# aquapi2.net
KiCad netlist of a schematic drawn in EAGLE
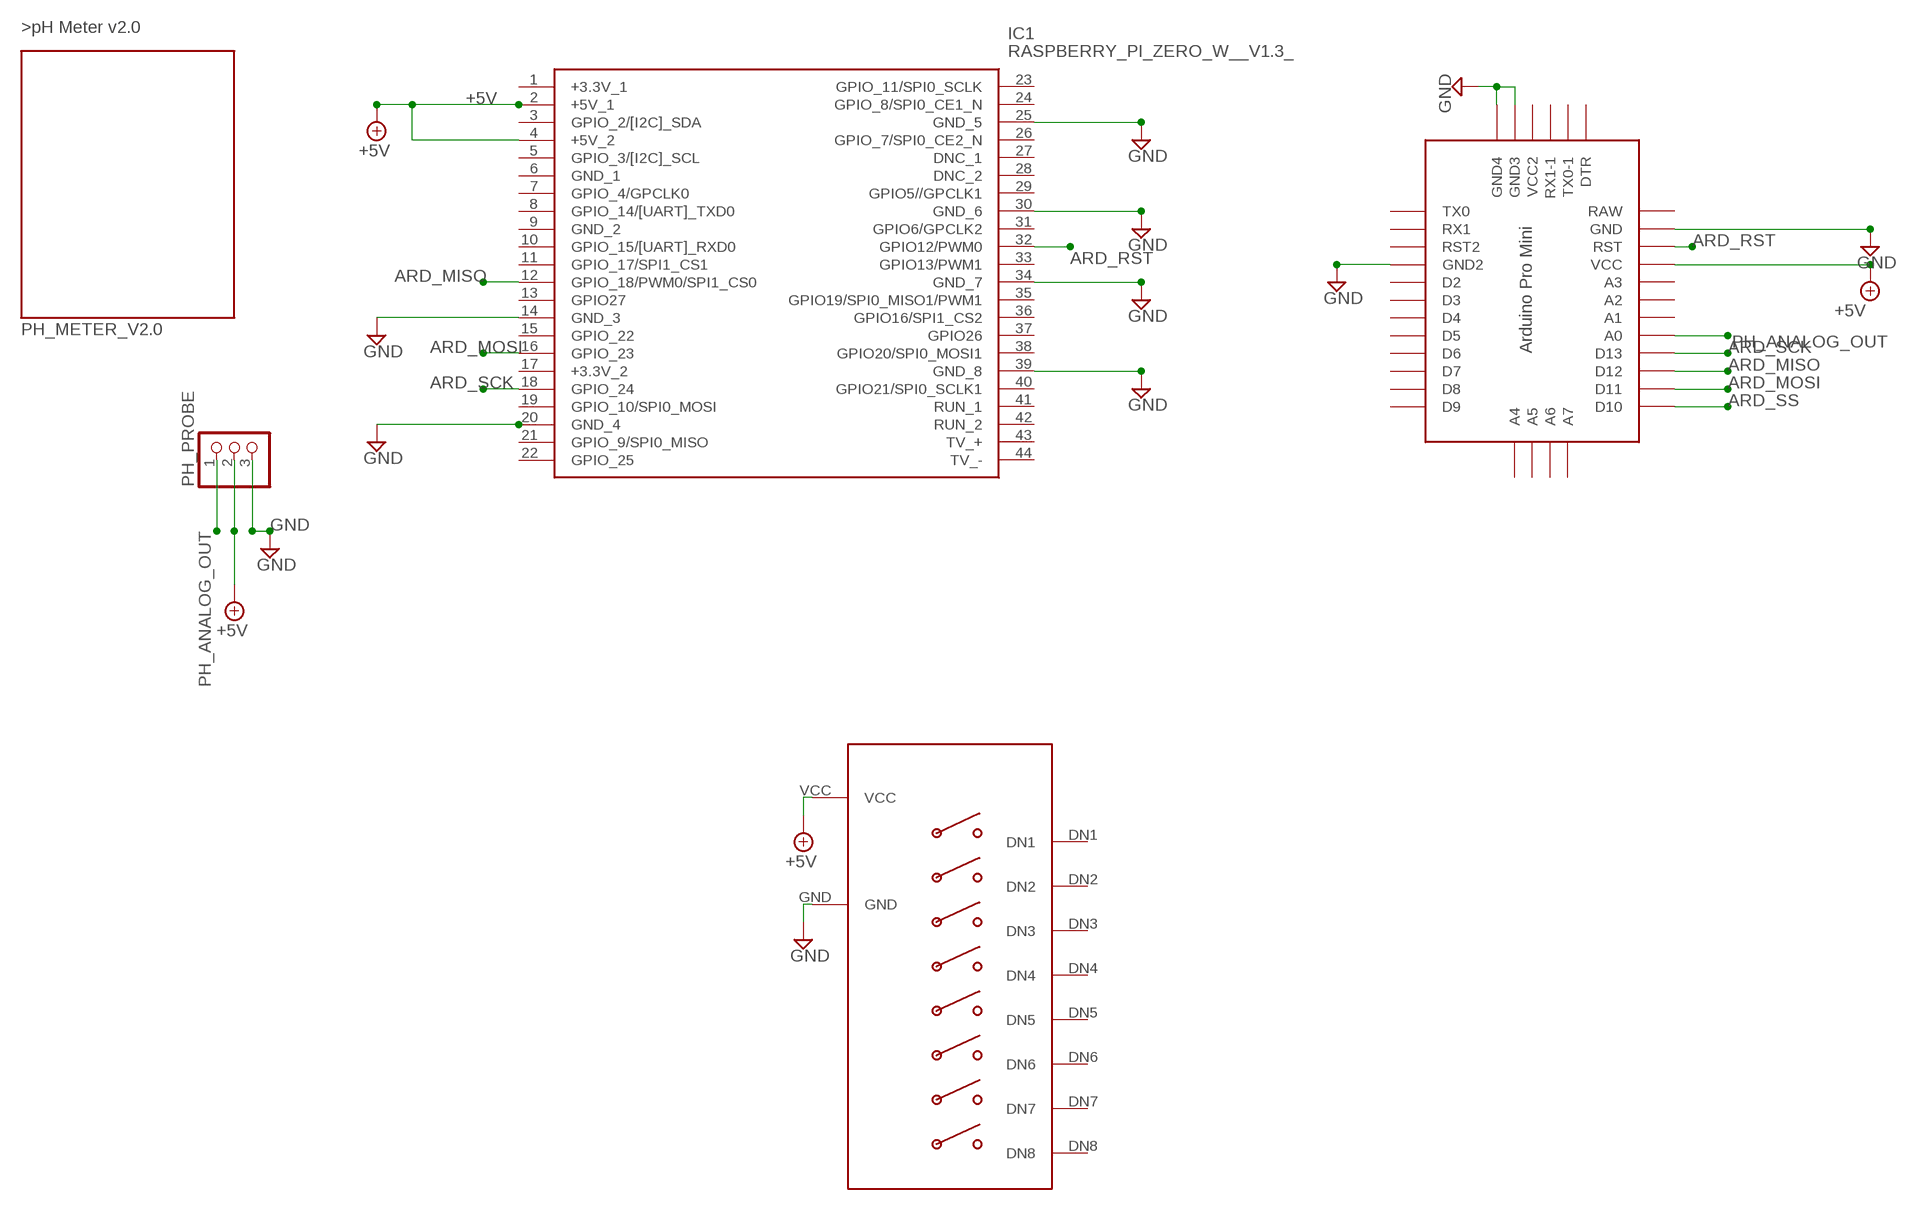
[diagram p0: schematic, sheet 1]

(export (version "E")
  (design (tool "Eeschema 10.0.6"))
  (components
    (comp (ref "IC1")
      (value "RASPBERRY_PI_ZERO_W__V1.3_")
      (footprint "eagle-import:RASPBERRYPIZEROWV13")
      (fields (field (name "MANUFACTURER_PART_NUMBER") "Raspberry Pi Zero W (v1.3)"))
      (libsource (lib "eagle-import") (part "RASPBERRY_PI_ZERO_W__V1.3_"))
    )
    (comp (ref "PH_PROBE")
      (value "PINHD-1X3")
      (footprint "eagle-import:1X03")
      (libsource (lib "eagle-import") (part "PINHD-1X3"))
    )
    (comp (ref "U$1")
      (value "PH_METER_V2.0")
      (footprint "eagle-import:PH_METER_V2.0")
      (libsource (lib "eagle-import") (part "PH_METER_V2.0"))
    )
    (comp (ref "U$2")
      (value "PRO-MINI")
      (footprint "eagle-import:PRO-MINI")
      (libsource (lib "eagle-import") (part "PRO-MINI"))
    )
    (comp (ref "U$3")
      (value "RELAY_X8")
      (footprint "eagle-import:RELAY_X8")
      (libsource (lib "eagle-import") (part "RELAY_X8"))
    )
  )
  (nets
    (net (code "1") (name "+5V") (class "Default")
      (node (ref "IC1") (pin "2") (pinfunction "+5V_1_2") (pintype "bidirectional"))
      (node (ref "IC1") (pin "4") (pinfunction "+5V_2_4") (pintype "bidirectional"))
      (node (ref "PH_PROBE") (pin "2") (pinfunction "2_2") (pintype "passive"))
      (node (ref "U$2") (pin "VCC") (pinfunction "VCC_VCC") (pintype "bidirectional"))
      (node (ref "U$3") (pin "VCC") (pinfunction "VCC_VCC") (pintype "bidirectional"))
    )
    (net (code "2") (name "/ARD_MISO") (class "Default")
      (node (ref "IC1") (pin "12") (pinfunction "GPIO_18/PWM0/SPI1_CS0_12") (pintype "bidirectional"))
      (node (ref "U$2") (pin "D12") (pinfunction "D12_D12") (pintype "bidirectional"))
    )
    (net (code "3") (name "/ARD_MOSI") (class "Default")
      (node (ref "IC1") (pin "16") (pinfunction "GPIO_23_16") (pintype "bidirectional"))
      (node (ref "U$2") (pin "D11") (pinfunction "D11_D11") (pintype "bidirectional"))
    )
    (net (code "4") (name "/ARD_RST") (class "Default")
      (node (ref "IC1") (pin "32") (pinfunction "GPIO12/PWM0_32") (pintype "bidirectional"))
      (node (ref "U$2") (pin "RST") (pinfunction "RST_RST") (pintype "bidirectional"))
    )
    (net (code "5") (name "/ARD_SCK") (class "Default")
      (node (ref "IC1") (pin "18") (pinfunction "GPIO_24_18") (pintype "bidirectional"))
      (node (ref "U$2") (pin "D13") (pinfunction "D13_D13") (pintype "bidirectional"))
    )
    (net (code "6") (name "/ARD_SS") (class "Default")
      (node (ref "U$2") (pin "D10") (pinfunction "D10_D10") (pintype "bidirectional"))
    )
    (net (code "7") (name "/PH_ANALOG_OUT") (class "Default")
      (node (ref "PH_PROBE") (pin "1") (pinfunction "1_1") (pintype "passive"))
      (node (ref "U$2") (pin "A0") (pinfunction "A0_A0") (pintype "bidirectional"))
    )
    (net (code "8") (name "/RAW") (class "Default")
      (node (ref "U$2") (pin "RAW") (pinfunction "RAW_RAW") (pintype "power_in"))
    )
    (net (code "9") (name "GND") (class "Default")
      (node (ref "IC1") (pin "14") (pinfunction "GND_3_14") (pintype "bidirectional"))
      (node (ref "IC1") (pin "20") (pinfunction "GND_4_20") (pintype "bidirectional"))
      (node (ref "IC1") (pin "25") (pinfunction "GND_5_25") (pintype "bidirectional"))
      (node (ref "IC1") (pin "30") (pinfunction "GND_6_30") (pintype "bidirectional"))
      (node (ref "IC1") (pin "34") (pinfunction "GND_7_34") (pintype "bidirectional"))
      (node (ref "IC1") (pin "39") (pinfunction "GND_8_39") (pintype "bidirectional"))
      (node (ref "PH_PROBE") (pin "3") (pinfunction "3_3") (pintype "passive"))
      (node (ref "U$2") (pin "GND") (pinfunction "GND_GND") (pintype "input"))
      (node (ref "U$2") (pin "GND1") (pinfunction "GND2_GND1") (pintype "bidirectional"))
      (node (ref "U$2") (pin "GND2") (pinfunction "GND4_GND2") (pintype "bidirectional"))
      (node (ref "U$2") (pin "GND3") (pinfunction "GND3_GND3") (pintype "bidirectional"))
      (node (ref "U$3") (pin "GND") (pinfunction "GND_GND") (pintype "bidirectional"))
    )
    (net (code "10") (name "unconnected-(IC1-+3.3V_1-Pad1)") (class "Default")
      (node (ref "IC1") (pin "1") (pinfunction "+3.3V_1_1") (pintype "bidirectional"))
    )
    (net (code "11") (name "unconnected-(IC1-+3.3V_2-Pad17)") (class "Default")
      (node (ref "IC1") (pin "17") (pinfunction "+3.3V_2_17") (pintype "bidirectional"))
    )
    (net (code "12") (name "unconnected-(IC1-DNC_1-Pad27)") (class "Default")
      (node (ref "IC1") (pin "27") (pinfunction "DNC_1_27") (pintype "bidirectional"))
    )
    (net (code "13") (name "unconnected-(IC1-DNC_2-Pad28)") (class "Default")
      (node (ref "IC1") (pin "28") (pinfunction "DNC_2_28") (pintype "bidirectional"))
    )
    (net (code "14") (name "unconnected-(IC1-GND_1-Pad6)") (class "Default")
      (node (ref "IC1") (pin "6") (pinfunction "GND_1_6") (pintype "bidirectional"))
    )
    (net (code "15") (name "unconnected-(IC1-GND_2-Pad9)") (class "Default")
      (node (ref "IC1") (pin "9") (pinfunction "GND_2_9") (pintype "bidirectional"))
    )
    (net (code "16") (name "unconnected-(IC1-GPIO5{slash}{slash}GPCLK1-Pad29)") (class "Default")
      (node (ref "IC1") (pin "29") (pinfunction "GPIO5//GPCLK1_29") (pintype "bidirectional"))
    )
    (net (code "17") (name "unconnected-(IC1-GPIO6{slash}GPCLK2-Pad31)") (class "Default")
      (node (ref "IC1") (pin "31") (pinfunction "GPIO6/GPCLK2_31") (pintype "bidirectional"))
    )
    (net (code "18") (name "unconnected-(IC1-GPIO13{slash}PWM1-Pad33)") (class "Default")
      (node (ref "IC1") (pin "33") (pinfunction "GPIO13/PWM1_33") (pintype "bidirectional"))
    )
    (net (code "19") (name "unconnected-(IC1-GPIO16{slash}SPI1_CS2-Pad36)") (class "Default")
      (node (ref "IC1") (pin "36") (pinfunction "GPIO16/SPI1_CS2_36") (pintype "bidirectional"))
    )
    (net (code "20") (name "unconnected-(IC1-GPIO19{slash}SPI0_MISO1{slash}PWM1-Pad35)") (class "Default")
      (node (ref "IC1") (pin "35") (pinfunction "GPIO19/SPI0_MISO1/PWM1_35") (pintype "bidirectional"))
    )
    (net (code "21") (name "unconnected-(IC1-GPIO20{slash}SPI0_MOSI1-Pad38)") (class "Default")
      (node (ref "IC1") (pin "38") (pinfunction "GPIO20/SPI0_MOSI1_38") (pintype "bidirectional"))
    )
    (net (code "22") (name "unconnected-(IC1-GPIO21{slash}SPI0_SCLK1-Pad40)") (class "Default")
      (node (ref "IC1") (pin "40") (pinfunction "GPIO21/SPI0_SCLK1_40") (pintype "bidirectional"))
    )
    (net (code "23") (name "unconnected-(IC1-GPIO26-Pad37)") (class "Default")
      (node (ref "IC1") (pin "37") (pinfunction "GPIO26_37") (pintype "bidirectional"))
    )
    (net (code "24") (name "unconnected-(IC1-GPIO27-Pad13)") (class "Default")
      (node (ref "IC1") (pin "13") (pinfunction "GPIO27_13") (pintype "bidirectional"))
    )
    (net (code "25") (name "unconnected-(IC1-GPIO_2{slash}[I2C]_SDA-Pad3)") (class "Default")
      (node (ref "IC1") (pin "3") (pinfunction "GPIO_2/[I2C]_SDA_3") (pintype "bidirectional"))
    )
    (net (code "26") (name "unconnected-(IC1-GPIO_3{slash}[I2C]_SCL-Pad5)") (class "Default")
      (node (ref "IC1") (pin "5") (pinfunction "GPIO_3/[I2C]_SCL_5") (pintype "bidirectional"))
    )
    (net (code "27") (name "unconnected-(IC1-GPIO_4{slash}GPCLK0-Pad7)") (class "Default")
      (node (ref "IC1") (pin "7") (pinfunction "GPIO_4/GPCLK0_7") (pintype "bidirectional"))
    )
    (net (code "28") (name "unconnected-(IC1-GPIO_7{slash}SPI0_CE2_N-Pad26)") (class "Default")
      (node (ref "IC1") (pin "26") (pinfunction "GPIO_7/SPI0_CE2_N_26") (pintype "bidirectional"))
    )
    (net (code "29") (name "unconnected-(IC1-GPIO_8{slash}SPI0_CE1_N-Pad24)") (class "Default")
      (node (ref "IC1") (pin "24") (pinfunction "GPIO_8/SPI0_CE1_N_24") (pintype "bidirectional"))
    )
    (net (code "30") (name "unconnected-(IC1-GPIO_9{slash}SPI0_MISO-Pad21)") (class "Default")
      (node (ref "IC1") (pin "21") (pinfunction "GPIO_9/SPI0_MISO_21") (pintype "bidirectional"))
    )
    (net (code "31") (name "unconnected-(IC1-GPIO_10{slash}SPI0_MOSI-Pad19)") (class "Default")
      (node (ref "IC1") (pin "19") (pinfunction "GPIO_10/SPI0_MOSI_19") (pintype "bidirectional"))
    )
    (net (code "32") (name "unconnected-(IC1-GPIO_11{slash}SPI0_SCLK-Pad23)") (class "Default")
      (node (ref "IC1") (pin "23") (pinfunction "GPIO_11/SPI0_SCLK_23") (pintype "bidirectional"))
    )
    (net (code "33") (name "unconnected-(IC1-GPIO_14{slash}[UART]_TXD0-Pad8)") (class "Default")
      (node (ref "IC1") (pin "8") (pinfunction "GPIO_14/[UART]_TXD0_8") (pintype "bidirectional"))
    )
    (net (code "34") (name "unconnected-(IC1-GPIO_15{slash}[UART]_RXD0-Pad10)") (class "Default")
      (node (ref "IC1") (pin "10") (pinfunction "GPIO_15/[UART]_RXD0_10") (pintype "bidirectional"))
    )
    (net (code "35") (name "unconnected-(IC1-GPIO_17{slash}SPI1_CS1-Pad11)") (class "Default")
      (node (ref "IC1") (pin "11") (pinfunction "GPIO_17/SPI1_CS1_11") (pintype "bidirectional"))
    )
    (net (code "36") (name "unconnected-(IC1-GPIO_22-Pad15)") (class "Default")
      (node (ref "IC1") (pin "15") (pinfunction "GPIO_22_15") (pintype "bidirectional"))
    )
    (net (code "37") (name "unconnected-(IC1-GPIO_25-Pad22)") (class "Default")
      (node (ref "IC1") (pin "22") (pinfunction "GPIO_25_22") (pintype "bidirectional"))
    )
    (net (code "38") (name "unconnected-(IC1-RUN_1-Pad41)") (class "Default")
      (node (ref "IC1") (pin "41") (pinfunction "RUN_1_41") (pintype "bidirectional"))
    )
    (net (code "39") (name "unconnected-(IC1-RUN_2-Pad42)") (class "Default")
      (node (ref "IC1") (pin "42") (pinfunction "RUN_2_42") (pintype "bidirectional"))
    )
    (net (code "40") (name "unconnected-(IC1-TV_+-Pad43)") (class "Default")
      (node (ref "IC1") (pin "43") (pinfunction "TV_+_43") (pintype "bidirectional"))
    )
    (net (code "41") (name "unconnected-(IC1-TV_--Pad44)") (class "Default")
      (node (ref "IC1") (pin "44") (pinfunction "TV_-_44") (pintype "bidirectional"))
    )
    (net (code "42") (name "unconnected-(U$2-PadA1)") (class "Default")
      (node (ref "U$2") (pin "A1") (pinfunction "A1_A1") (pintype "bidirectional"))
    )
    (net (code "43") (name "unconnected-(U$2-PadA2)") (class "Default")
      (node (ref "U$2") (pin "A2") (pinfunction "A2_A2") (pintype "bidirectional"))
    )
    (net (code "44") (name "unconnected-(U$2-PadA3)") (class "Default")
      (node (ref "U$2") (pin "A3") (pinfunction "A3_A3") (pintype "bidirectional"))
    )
    (net (code "45") (name "unconnected-(U$2-PadA4)") (class "Default")
      (node (ref "U$2") (pin "A4") (pinfunction "A4_A4") (pintype "bidirectional"))
    )
    (net (code "46") (name "unconnected-(U$2-PadA5)") (class "Default")
      (node (ref "U$2") (pin "A5") (pinfunction "A5_A5") (pintype "bidirectional"))
    )
    (net (code "47") (name "unconnected-(U$2-PadA6)") (class "Default")
      (node (ref "U$2") (pin "A6") (pinfunction "A6_A6") (pintype "bidirectional"))
    )
    (net (code "48") (name "unconnected-(U$2-PadA7)") (class "Default")
      (node (ref "U$2") (pin "A7") (pinfunction "A7_A7") (pintype "bidirectional"))
    )
    (net (code "49") (name "unconnected-(U$2-PadD2)") (class "Default")
      (node (ref "U$2") (pin "D2") (pinfunction "D2_D2") (pintype "bidirectional"))
    )
    (net (code "50") (name "unconnected-(U$2-PadD3)") (class "Default")
      (node (ref "U$2") (pin "D3") (pinfunction "D3_D3") (pintype "bidirectional"))
    )
    (net (code "51") (name "unconnected-(U$2-PadD4)") (class "Default")
      (node (ref "U$2") (pin "D4") (pinfunction "D4_D4") (pintype "bidirectional"))
    )
    (net (code "52") (name "unconnected-(U$2-PadD5)") (class "Default")
      (node (ref "U$2") (pin "D5") (pinfunction "D5_D5") (pintype "bidirectional"))
    )
    (net (code "53") (name "unconnected-(U$2-PadD6)") (class "Default")
      (node (ref "U$2") (pin "D6") (pinfunction "D6_D6") (pintype "bidirectional"))
    )
    (net (code "54") (name "unconnected-(U$2-PadD7)") (class "Default")
      (node (ref "U$2") (pin "D7") (pinfunction "D7_D7") (pintype "bidirectional"))
    )
    (net (code "55") (name "unconnected-(U$2-PadD8)") (class "Default")
      (node (ref "U$2") (pin "D8") (pinfunction "D8_D8") (pintype "bidirectional"))
    )
    (net (code "56") (name "unconnected-(U$2-PadD9)") (class "Default")
      (node (ref "U$2") (pin "D9") (pinfunction "D9_D9") (pintype "bidirectional"))
    )
    (net (code "57") (name "unconnected-(U$2-PadDTR)") (class "Default")
      (node (ref "U$2") (pin "DTR") (pinfunction "DTR_DTR") (pintype "bidirectional"))
    )
    (net (code "58") (name "unconnected-(U$2-PadRX1)") (class "Default")
      (node (ref "U$2") (pin "RX1") (pinfunction "RX1_RX1") (pintype "bidirectional"))
    )
    (net (code "59") (name "unconnected-(U$2-PadRX1-1)") (class "Default")
      (node (ref "U$2") (pin "RX1-1") (pinfunction "RX1-1_RX1-1") (pintype "bidirectional"))
    )
    (net (code "60") (name "unconnected-(U$2-PadTX0)") (class "Default")
      (node (ref "U$2") (pin "TX0") (pinfunction "TX0_TX0") (pintype "bidirectional"))
    )
    (net (code "61") (name "unconnected-(U$2-PadTX0-1)") (class "Default")
      (node (ref "U$2") (pin "TX0-1") (pinfunction "TX0-1_TX0-1") (pintype "bidirectional"))
    )
    (net (code "62") (name "unconnected-(U$2-RST2-PadRST1)") (class "Default")
      (node (ref "U$2") (pin "RST1") (pinfunction "RST2_RST1") (pintype "bidirectional"))
    )
    (net (code "63") (name "unconnected-(U$2-VCC2-PadVCC1)") (class "Default")
      (node (ref "U$2") (pin "VCC1") (pinfunction "VCC2_VCC1") (pintype "bidirectional"))
    )
    (net (code "64") (name "unconnected-(U$3-PadDN1)") (class "Default")
      (node (ref "U$3") (pin "DN1") (pinfunction "DN1_DN1") (pintype "bidirectional"))
    )
    (net (code "65") (name "unconnected-(U$3-PadDN2)") (class "Default")
      (node (ref "U$3") (pin "DN2") (pinfunction "DN2_DN2") (pintype "bidirectional"))
    )
    (net (code "66") (name "unconnected-(U$3-PadDN3)") (class "Default")
      (node (ref "U$3") (pin "DN3") (pinfunction "DN3_DN3") (pintype "bidirectional"))
    )
    (net (code "67") (name "unconnected-(U$3-PadDN4)") (class "Default")
      (node (ref "U$3") (pin "DN4") (pinfunction "DN4_DN4") (pintype "bidirectional"))
    )
    (net (code "68") (name "unconnected-(U$3-PadDN5)") (class "Default")
      (node (ref "U$3") (pin "DN5") (pinfunction "DN5_DN5") (pintype "bidirectional"))
    )
    (net (code "69") (name "unconnected-(U$3-PadDN6)") (class "Default")
      (node (ref "U$3") (pin "DN6") (pinfunction "DN6_DN6") (pintype "bidirectional"))
    )
    (net (code "70") (name "unconnected-(U$3-PadDN7)") (class "Default")
      (node (ref "U$3") (pin "DN7") (pinfunction "DN7_DN7") (pintype "bidirectional"))
    )
    (net (code "71") (name "unconnected-(U$3-PadDN8)") (class "Default")
      (node (ref "U$3") (pin "DN8") (pinfunction "DN8_DN8") (pintype "bidirectional"))
    )
  )
)
